# SCH_Avionic1_2026-04-20.net
KiCad netlist of a schematic drawn in EasyEDA
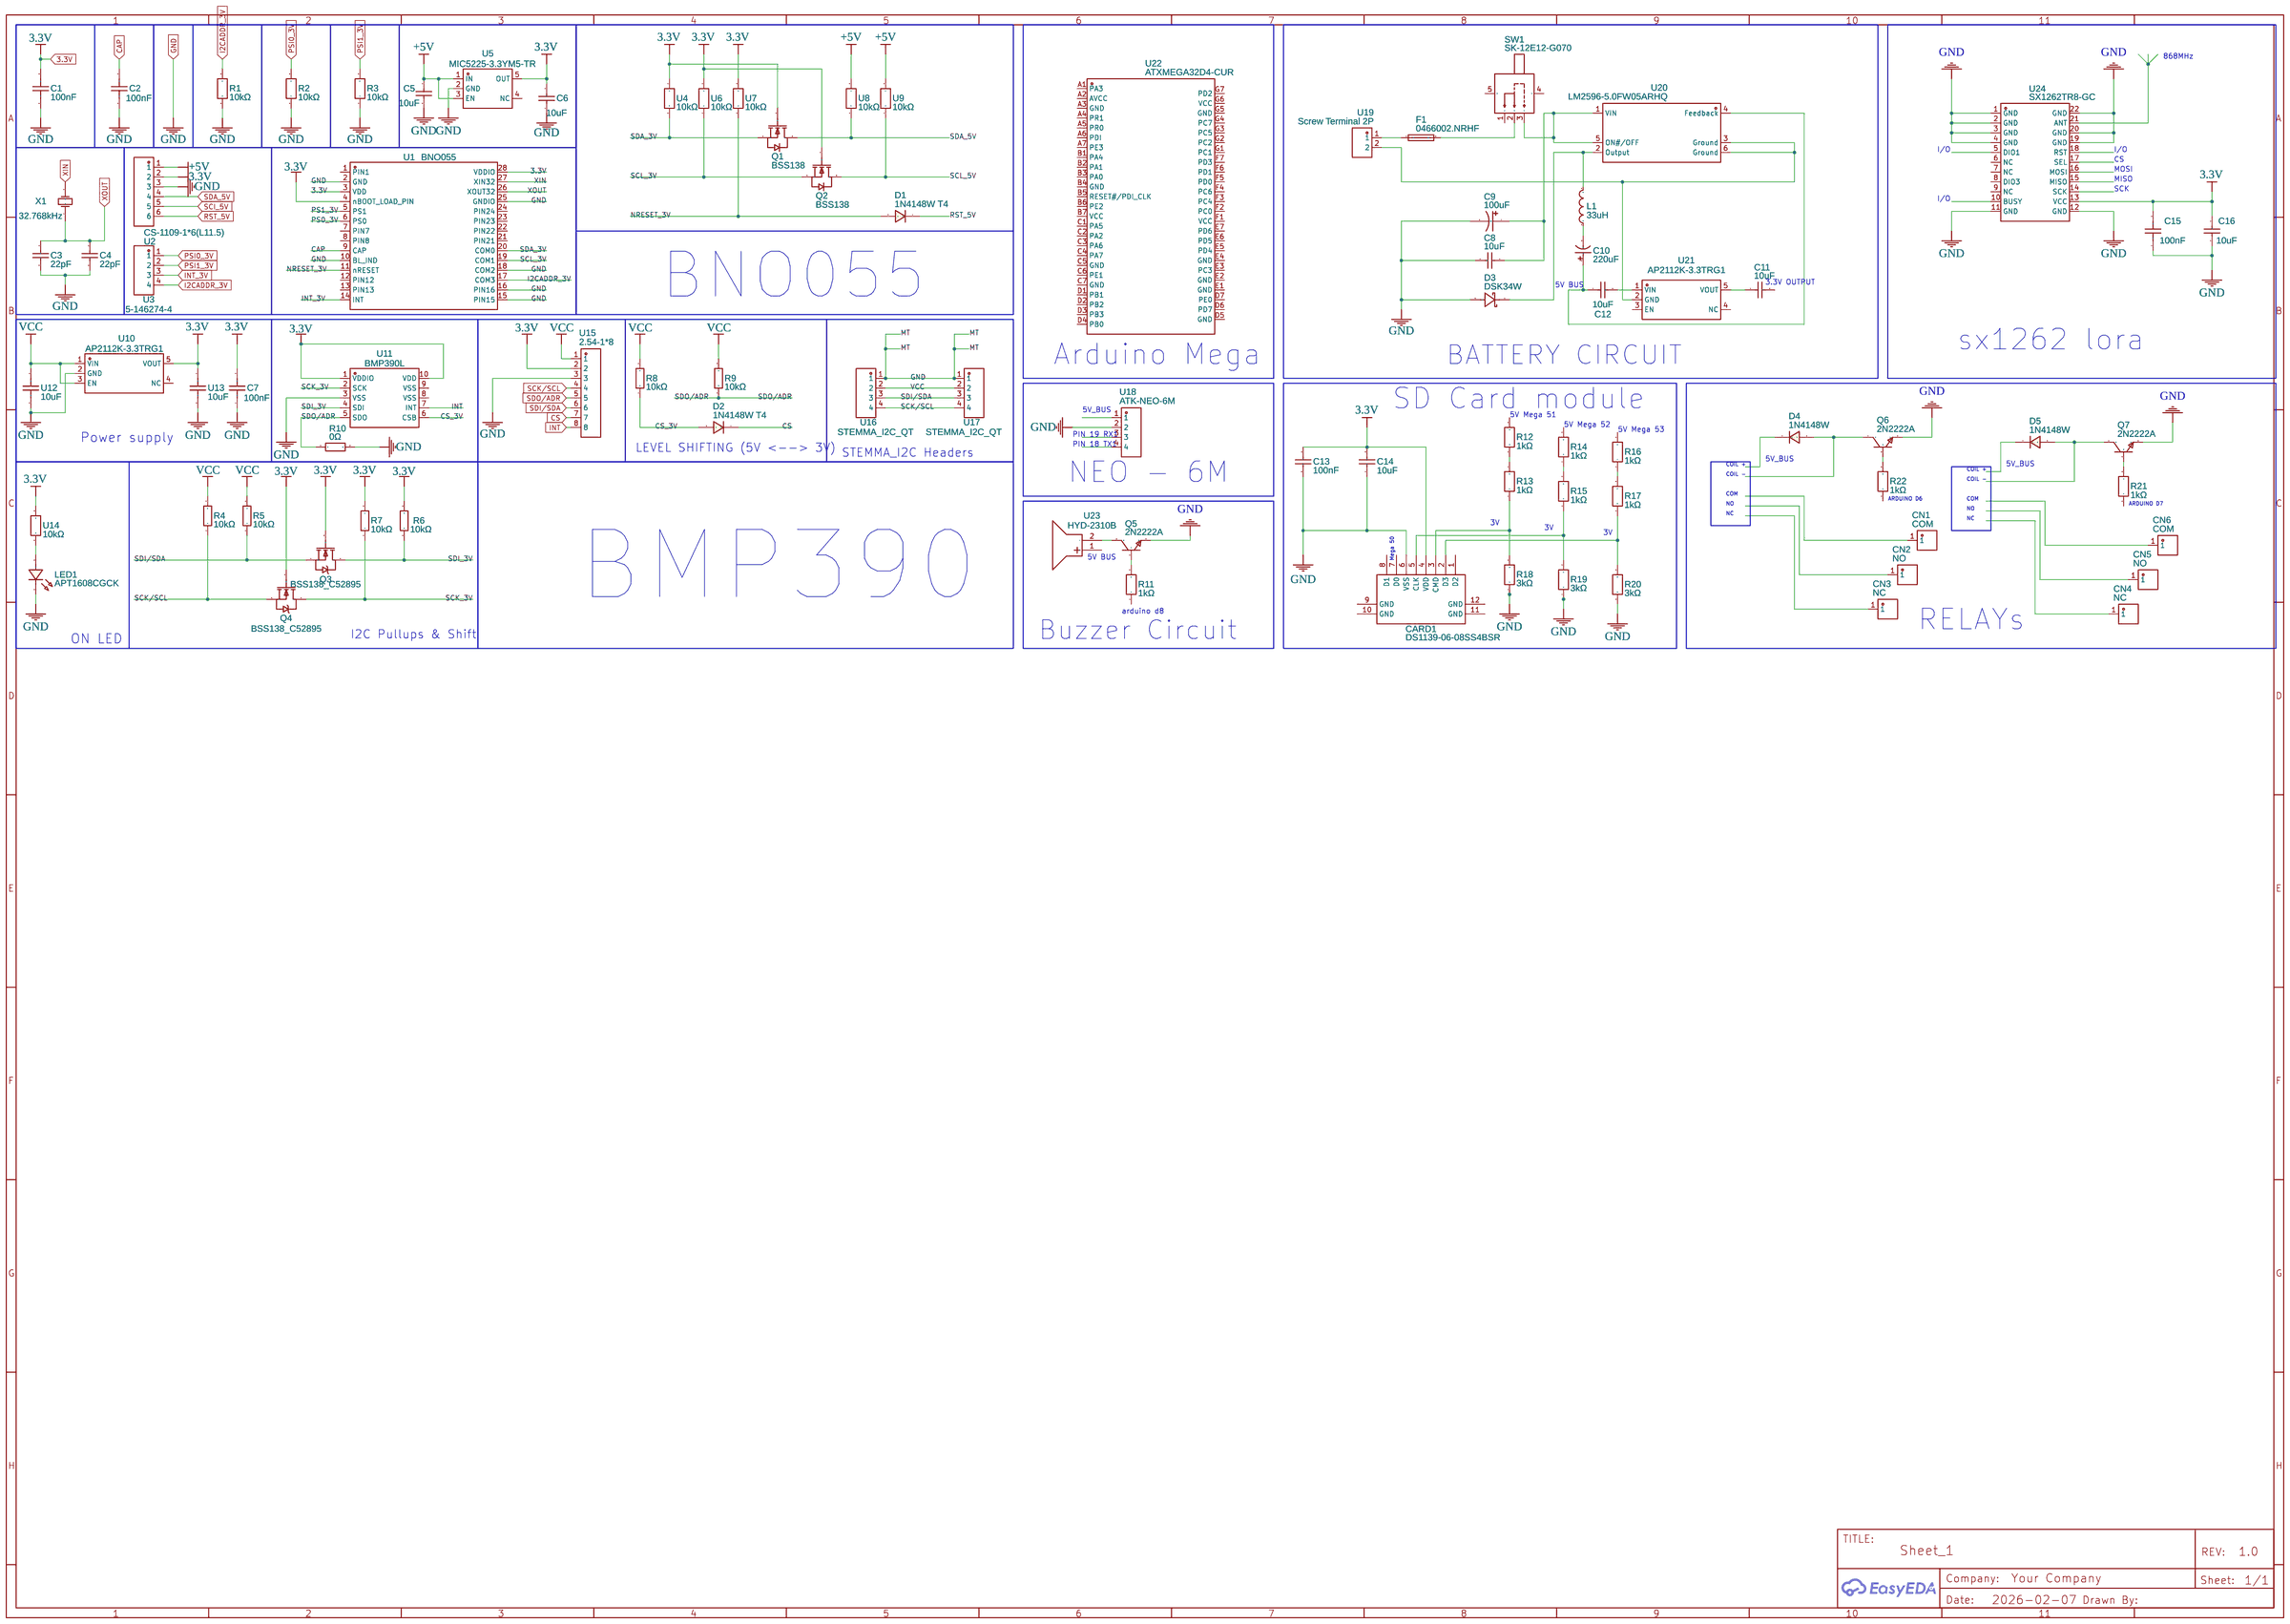
[diagram p0: schematic sheet]

(export (version "E")
  (design (tool "Eeschema 10.0.6"))
  (components
    (comp (ref "C1")
      (value "100nF")
      (fields
        (field (name "Manufacturer Part") "CL05B104KO5NNNC")
        (field (name "Manufacturer") "SAMSUNG(三星)")
      )
      (libsource (lib "") (part "CL05B104KO5NNNC"))
    )
    (comp (ref "C2")
      (value "100nF")
      (fields
        (field (name "Manufacturer Part") "CL05B104KO5NNNC")
        (field (name "Manufacturer") "SAMSUNG(三星)")
      )
      (libsource (lib "") (part "CL05B104KO5NNNC"))
    )
    (comp (ref "C3")
      (value "22pF")
      (fields
        (field (name "Manufacturer Part") "CL10C220JB8NNNC")
        (field (name "Manufacturer") "SAMSUNG(三星)")
      )
      (libsource (lib "") (part "CL10C220JB8NNNC"))
    )
    (comp (ref "C4")
      (value "22pF")
      (fields
        (field (name "Manufacturer Part") "CL10C220JB8NNNC")
        (field (name "Manufacturer") "SAMSUNG(三星)")
      )
      (libsource (lib "") (part "CL10C220JB8NNNC"))
    )
    (comp (ref "C5")
      (value "10uF")
      (fields
        (field (name "Manufacturer Part") "CL21A106KOQNNNE")
        (field (name "Manufacturer") "SAMSUNG(三星)")
      )
      (libsource (lib "") (part "CL21A106KOQNNNE_1"))
    )
    (comp (ref "C6")
      (value "10uF")
      (fields
        (field (name "Manufacturer Part") "CL21A106KOQNNNE")
        (field (name "Manufacturer") "SAMSUNG(三星)")
      )
      (libsource (lib "") (part "CL21A106KOQNNNE_2"))
    )
    (comp (ref "C7")
      (value "100nF")
      (fields
        (field (name "Manufacturer Part") "CC0402KRX5R6BB104")
        (field (name "Manufacturer") "YAGEO(国巨)")
      )
      (libsource (lib "") (part "CC0402KRX5R6BB104"))
    )
    (comp (ref "C8")
      (value "10uF")
      (fields
        (field (name "Manufacturer Part") "CL21A106KOQNNNE")
        (field (name "Manufacturer") "SAMSUNG(三星)")
      )
      (libsource (lib "") (part "CL21A106KOQNNNE"))
    )
    (comp (ref "C9")
      (value "100uF")
      (fields
        (field (name "Manufacturer Part") "NXA25V100M6.3*11 2.5TP")
        (field (name "Manufacturer") "SAMYOUNG(韩国三莹)")
      )
      (libsource (lib "") (part "NXA 25V100 6.3*11"))
    )
    (comp (ref "C10")
      (value "220uF")
      (fields
        (field (name "Manufacturer Part") "MHA 16V220 6.3*11")
        (field (name "Manufacturer") "SAMYOUNG(韩国三莹)")
      )
      (libsource (lib "") (part "MHA-16V220-6.3*11"))
    )
    (comp (ref "C11")
      (value "10uF")
      (fields
        (field (name "Manufacturer Part") "CL21A106KOQNNNE")
        (field (name "Manufacturer") "SAMSUNG(三星)")
      )
      (libsource (lib "") (part "CL21A106KOQNNNE"))
    )
    (comp (ref "C12")
      (value "10uF")
      (fields
        (field (name "Manufacturer Part") "CL21A106KOQNNNE")
        (field (name "Manufacturer") "SAMSUNG(三星)")
      )
      (libsource (lib "") (part "CL21A106KOQNNNE"))
    )
    (comp (ref "C13")
      (value "100nF")
      (fields
        (field (name "Manufacturer Part") "CL10B104KA8NNNC")
        (field (name "Manufacturer") "SAMSUNG(三星)")
      )
      (libsource (lib "") (part "CL10B104KA8NNNC"))
    )
    (comp (ref "C14")
      (value "10uF")
      (fields
        (field (name "Manufacturer Part") "CL21A106KOQNNNE")
        (field (name "Manufacturer") "SAMSUNG(三星)")
      )
      (libsource (lib "") (part "CL21A106KOQNNNE_2"))
    )
    (comp (ref "C15")
      (value "100nF")
      (fields
        (field (name "Manufacturer Part") "CL05B104KO5NNNC")
        (field (name "Manufacturer") "SAMSUNG(三星)")
      )
      (libsource (lib "") (part "CL05B104KO5NNNC"))
    )
    (comp (ref "C16")
      (value "10uF")
      (fields
        (field (name "Manufacturer Part") "CL21A106KOQNNNE")
        (field (name "Manufacturer") "SAMSUNG(三星)")
      )
      (libsource (lib "") (part "CL21A106KOQNNNE_1"))
    )
    (comp (ref "CARD1")
      (value "DS1139-06-08SS4BSR")
      (fields (field (name "Manufacturer") "CONNFLY"))
      (libsource (lib "") (part "DS1139-06-08SS4BSR"))
    )
    (comp (ref "CN1")
      (value "COM")
      (fields
        (field (name "Manufacturer Part") "DB2EK-5.08-3P-GN-S")
        (field (name "Manufacturer") "DORABO(地博电气)")
      )
      (libsource (lib "") (part "DB2EK-5.08-3P-GN-S"))
    )
    (comp (ref "CN2")
      (value "NO")
      (fields
        (field (name "Manufacturer Part") "DB2EK-5.08-3P-GN-S")
        (field (name "Manufacturer") "DORABO(地博电气)")
      )
      (libsource (lib "") (part "DB2EK-5.08-3P-GN-S"))
    )
    (comp (ref "CN3")
      (value "NC")
      (fields
        (field (name "Manufacturer Part") "DB2EK-5.08-3P-GN-S")
        (field (name "Manufacturer") "DORABO(地博电气)")
      )
      (libsource (lib "") (part "DB2EK-5.08-3P-GN-S"))
    )
    (comp (ref "CN4")
      (value "NC")
      (fields
        (field (name "Manufacturer Part") "DB2EK-5.08-3P-GN-S")
        (field (name "Manufacturer") "DORABO(地博电气)")
      )
      (libsource (lib "") (part "DB2EK-5.08-3P-GN-S"))
    )
    (comp (ref "CN5")
      (value "NO")
      (fields
        (field (name "Manufacturer Part") "DB2EK-5.08-3P-GN-S")
        (field (name "Manufacturer") "DORABO(地博电气)")
      )
      (libsource (lib "") (part "DB2EK-5.08-3P-GN-S"))
    )
    (comp (ref "CN6")
      (value "COM")
      (fields
        (field (name "Manufacturer Part") "DB2EK-5.08-3P-GN-S")
        (field (name "Manufacturer") "DORABO(地博电气)")
      )
      (libsource (lib "") (part "DB2EK-5.08-3P-GN-S"))
    )
    (comp (ref "D1")
      (value "1N4148W T4")
      (fields (field (name "Manufacturer Part") "1N4148W") (field (name "Manufacturer") "CJ(江苏长电/长晶)"))
      (libsource (lib "") (part "1N4148W T4"))
    )
    (comp (ref "D2")
      (value "1N4148W T4")
      (fields (field (name "Manufacturer Part") "1N4148W") (field (name "Manufacturer") "CJ(江苏长电/长晶)"))
      (libsource (lib "") (part "1N4148W T4"))
    )
    (comp (ref "D3")
      (value "DSK34W")
      (fields (field (name "Manufacturer") "FOSAN(富捷/富信)"))
      (libsource (lib "") (part "DSK34W"))
    )
    (comp (ref "D4")
      (value "1N4148W")
      (fields (field (name "Manufacturer") "HT(金誉)"))
      (libsource (lib "") (part "1N4148W"))
    )
    (comp (ref "D5")
      (value "1N4148W")
      (fields (field (name "Manufacturer") "HT(金誉)"))
      (libsource (lib "") (part "1N4148W"))
    )
    (comp (ref "F1")
      (value "0466002.NRHF")
      (fields (field (name "Manufacturer") "Littelfuse(美国力特)"))
      (libsource (lib "") (part "0466002.NRHF"))
    )
    (comp (ref "L1")
      (value "33uH")
      (fields (field (name "Manufacturer Part") "CKCS5040-33uH/M") (field (name "Manufacturer") "CENKER(岑科)"))
      (libsource (lib "") (part "CKCS5040-33UH/M"))
    )
    (comp (ref "LED1")
      (value "APT1608CGCK")
      (fields (field (name "Manufacturer") "Kingbright"))
      (libsource (lib "") (part "APT1608CGCK"))
    )
    (comp (ref "Q1")
      (value "BSS138")
      (fields (field (name "Manufacturer") "CJ(江苏长电/长晶)"))
      (libsource (lib "") (part "BSS138"))
    )
    (comp (ref "Q2")
      (value "BSS138")
      (fields (field (name "Manufacturer") "CJ(江苏长电/长晶)"))
      (libsource (lib "") (part "BSS138"))
    )
    (comp (ref "Q3")
      (value "BSS138_C52895")
      (fields (field (name "Manufacturer Part") "BSS138") (field (name "Manufacturer") "onsemi(安森美)"))
      (libsource (lib "") (part "BSS138_C52895"))
    )
    (comp (ref "Q4")
      (value "BSS138_C52895")
      (fields (field (name "Manufacturer Part") "BSS138") (field (name "Manufacturer") "onsemi(安森美)"))
      (libsource (lib "") (part "BSS138_C52895"))
    )
    (comp (ref "Q5")
      (value "2N2222A")
      (fields (field (name "Manufacturer") "BLUE ROCKET(蓝箭)"))
      (libsource (lib "") (part "2N2222A"))
    )
    (comp (ref "Q6")
      (value "2N2222A")
      (fields (field (name "Manufacturer") "BLUE ROCKET(蓝箭)"))
      (libsource (lib "") (part "2N2222A"))
    )
    (comp (ref "Q7")
      (value "2N2222A")
      (fields (field (name "Manufacturer") "BLUE ROCKET(蓝箭)"))
      (libsource (lib "") (part "2N2222A"))
    )
    (comp (ref "R1")
      (value "10kΩ")
      (fields (field (name "Manufacturer Part") "0402 ±1% 10K") (field (name "Manufacturer") "VO(翔胜)"))
      (libsource (lib "") (part "0402 ±1% 10K"))
    )
    (comp (ref "R2")
      (value "10kΩ")
      (fields (field (name "Manufacturer Part") "0402 ±1% 10K") (field (name "Manufacturer") "VO(翔胜)"))
      (libsource (lib "") (part "0402 ±1% 10K"))
    )
    (comp (ref "R3")
      (value "10kΩ")
      (fields (field (name "Manufacturer Part") "0402 ±1% 10K") (field (name "Manufacturer") "VO(翔胜)"))
      (libsource (lib "") (part "0402 ±1% 10K"))
    )
    (comp (ref "R4")
      (value "10kΩ")
      (fields
        (field (name "Manufacturer Part") "0603WAJ0103T5E")
        (field (name "Manufacturer") "UNI-ROYAL(厚声)")
      )
      (libsource (lib "") (part "0603WAJ0103T5E"))
    )
    (comp (ref "R5")
      (value "10kΩ")
      (fields
        (field (name "Manufacturer Part") "0603WAJ0103T5E")
        (field (name "Manufacturer") "UNI-ROYAL(厚声)")
      )
      (libsource (lib "") (part "0603WAJ0103T5E"))
    )
    (comp (ref "R6")
      (value "10kΩ")
      (fields
        (field (name "Manufacturer Part") "0603WAJ0103T5E")
        (field (name "Manufacturer") "UNI-ROYAL(厚声)")
      )
      (libsource (lib "") (part "0603WAJ0103T5E"))
    )
    (comp (ref "R7")
      (value "10kΩ")
      (fields
        (field (name "Manufacturer Part") "0603WAJ0103T5E")
        (field (name "Manufacturer") "UNI-ROYAL(厚声)")
      )
      (libsource (lib "") (part "0603WAJ0103T5E"))
    )
    (comp (ref "R8")
      (value "10kΩ")
      (fields
        (field (name "Manufacturer Part") "0603WAJ0103T5E")
        (field (name "Manufacturer") "UNI-ROYAL(厚声)")
      )
      (libsource (lib "") (part "0603WAJ0103T5E"))
    )
    (comp (ref "R9")
      (value "10kΩ")
      (fields
        (field (name "Manufacturer Part") "0603WAJ0103T5E")
        (field (name "Manufacturer") "UNI-ROYAL(厚声)")
      )
      (libsource (lib "") (part "0603WAJ0103T5E"))
    )
    (comp (ref "R10")
      (value "0Ω")
      (fields (field (name "Manufacturer Part") "RCT030RLF") (field (name "Manufacturer") "HKR(香港电阻)"))
      (libsource (lib "") (part "RCT030RJLF"))
    )
    (comp (ref "R11")
      (value "1kΩ")
      (fields (field (name "Manufacturer Part") "RCT021KFLF") (field (name "Manufacturer") "HKR(香港电阻)"))
      (libsource (lib "") (part "RCT021KFLF"))
    )
    (comp (ref "R12")
      (value "1kΩ")
      (fields (field (name "Manufacturer Part") "RCT021KFLF") (field (name "Manufacturer") "HKR(香港电阻)"))
      (libsource (lib "") (part "RCT021KFLF"))
    )
    (comp (ref "R13")
      (value "1kΩ")
      (fields (field (name "Manufacturer Part") "RCT021KFLF") (field (name "Manufacturer") "HKR(香港电阻)"))
      (libsource (lib "") (part "RCT021KFLF"))
    )
    (comp (ref "R14")
      (value "1kΩ")
      (fields (field (name "Manufacturer Part") "RCT021KFLF") (field (name "Manufacturer") "HKR(香港电阻)"))
      (libsource (lib "") (part "RCT021KFLF"))
    )
    (comp (ref "R15")
      (value "1kΩ")
      (fields (field (name "Manufacturer Part") "RCT021KFLF") (field (name "Manufacturer") "HKR(香港电阻)"))
      (libsource (lib "") (part "RCT021KFLF"))
    )
    (comp (ref "R16")
      (value "1kΩ")
      (fields (field (name "Manufacturer Part") "RCT021KFLF") (field (name "Manufacturer") "HKR(香港电阻)"))
      (libsource (lib "") (part "RCT021KFLF"))
    )
    (comp (ref "R17")
      (value "1kΩ")
      (fields (field (name "Manufacturer Part") "RCT021KFLF") (field (name "Manufacturer") "HKR(香港电阻)"))
      (libsource (lib "") (part "RCT021KFLF"))
    )
    (comp (ref "R18")
      (value "3kΩ")
      (fields (field (name "Manufacturer Part") "RCT023KFLF") (field (name "Manufacturer") "HKR(香港电阻)"))
      (libsource (lib "") (part "RCT023KFLF"))
    )
    (comp (ref "R19")
      (value "3kΩ")
      (fields (field (name "Manufacturer Part") "RCT023KFLF") (field (name "Manufacturer") "HKR(香港电阻)"))
      (libsource (lib "") (part "RCT023KFLF"))
    )
    (comp (ref "R20")
      (value "3kΩ")
      (fields (field (name "Manufacturer Part") "RCT023KFLF") (field (name "Manufacturer") "HKR(香港电阻)"))
      (libsource (lib "") (part "RCT023KFLF"))
    )
    (comp (ref "R21")
      (value "1kΩ")
      (fields (field (name "Manufacturer Part") "RCT021KFLF") (field (name "Manufacturer") "HKR(香港电阻)"))
      (libsource (lib "") (part "RCT021KFLF"))
    )
    (comp (ref "R22")
      (value "1kΩ")
      (fields (field (name "Manufacturer Part") "RCT021KFLF") (field (name "Manufacturer") "HKR(香港电阻)"))
      (libsource (lib "") (part "RCT021KFLF"))
    )
    (comp (ref "SW1")
      (value "SK-12E12-G070")
      (fields (field (name "Manufacturer") "G-Switch(品赞)"))
      (libsource (lib "") (part "SK-12E12-G070"))
    )
    (comp (ref "U1")
      (value "BNO055")
      (fields (field (name "Manufacturer") "Bosch(博世)"))
      (libsource (lib "") (part "BNO055"))
    )
    (comp (ref "U2")
      (value "CS-1109-1*6(L11.5)")
      (fields (field (name "Manufacturer") "CST(永丰盈)"))
      (libsource (lib "") (part "CS-1109-1*6(L11.5)"))
    )
    (comp (ref "U3")
      (value "5-146274-4")
      (fields (field (name "Manufacturer") "TE Connectivity(泰科电子)"))
      (libsource (lib "") (part "5-146274-4"))
    )
    (comp (ref "U4")
      (value "10kΩ")
      (fields
        (field (name "Manufacturer Part") "HoLTT0603-1/10W-10K-1%")
        (field (name "Manufacturer") "Milliohm(毫欧)")
      )
      (libsource (lib "") (part "HOLTT0603-1/10W-10K-1%_1"))
    )
    (comp (ref "U5")
      (value "MIC5225-3.3YM5-TR")
      (fields (field (name "Manufacturer") "MICROCHIP(美国微芯)"))
      (libsource (lib "") (part "MIC5225-3.3YM5-TR"))
    )
    (comp (ref "U6")
      (value "10kΩ")
      (fields
        (field (name "Manufacturer Part") "HoLTT0603-1/10W-10K-1%")
        (field (name "Manufacturer") "Milliohm(毫欧)")
      )
      (libsource (lib "") (part "HOLTT0603-1/10W-10K-1%"))
    )
    (comp (ref "U7")
      (value "10kΩ")
      (fields
        (field (name "Manufacturer Part") "HoLTT0603-1/10W-10K-1%")
        (field (name "Manufacturer") "Milliohm(毫欧)")
      )
      (libsource (lib "") (part "HOLTT0603-1/10W-10K-1%"))
    )
    (comp (ref "U8")
      (value "10kΩ")
      (fields
        (field (name "Manufacturer Part") "HoLTT0603-1/10W-10K-1%")
        (field (name "Manufacturer") "Milliohm(毫欧)")
      )
      (libsource (lib "") (part "HOLTT0603-1/10W-10K-1%"))
    )
    (comp (ref "U9")
      (value "10kΩ")
      (fields
        (field (name "Manufacturer Part") "HoLTT0603-1/10W-10K-1%")
        (field (name "Manufacturer") "Milliohm(毫欧)")
      )
      (libsource (lib "") (part "HOLTT0603-1/10W-10K-1%"))
    )
    (comp (ref "U10")
      (value "AP2112K-3.3TRG1")
      (fields (field (name "Manufacturer") "DIODES(美台)"))
      (libsource (lib "") (part "AP2112K-3.3TRG1"))
    )
    (comp (ref "U11")
      (value "BMP390L")
      (fields (field (name "Manufacturer") "Bosch(博世)"))
      (libsource (lib "") (part "BMP390L"))
    )
    (comp (ref "U12")
      (value "10uF")
      (fields
        (field (name "Manufacturer Part") "CC0805KKX7R6BB106")
        (field (name "Manufacturer") "YAGEO(国巨)")
      )
      (libsource (lib "") (part "CC0805KKX7R6BB106"))
    )
    (comp (ref "U13")
      (value "10uF")
      (fields
        (field (name "Manufacturer Part") "CC0805KKX7R6BB106")
        (field (name "Manufacturer") "YAGEO(国巨)")
      )
      (libsource (lib "") (part "CC0805KKX7R6BB106"))
    )
    (comp (ref "U14")
      (value "10kΩ")
      (fields
        (field (name "Manufacturer Part") "HoLTT0603-1/10W-10K-1%")
        (field (name "Manufacturer") "Milliohm(毫欧)")
      )
      (libsource (lib "") (part "HOLTT0603-1/10W-10K-1%"))
    )
    (comp (ref "U15")
      (value "2.54-1*8")
      (fields (field (name "Manufacturer") "ZHOURI(洲日)"))
      (libsource (lib "") (part "2.54-1*8"))
    )
    (comp (ref "U16")
      (value "STEMMA_I2C_QT")
      (fields
        (field (name "Manufacturer Part") "5-146274-4")
        (field (name "Manufacturer") "TE Connectivity(泰科电子)")
      )
      (libsource (lib "") (part "5-146274-4"))
    )
    (comp (ref "U17")
      (value "STEMMA_I2C_QT")
      (fields
        (field (name "Manufacturer Part") "5-146274-4")
        (field (name "Manufacturer") "TE Connectivity(泰科电子)")
      )
      (libsource (lib "") (part "5-146274-4_1"))
    )
    (comp (ref "U18") (value "ATK-NEO-6M") (libsource (lib "") (part "ATK-NEO-6M")))
    (comp (ref "U19")
      (value "Screw Terminal 2P")
      (fields
        (field (name "Manufacturer Part") "WJ500V-5.08-02P-13-00A")
        (field (name "Manufacturer") "KANGNEX(康奈克斯电气)")
      )
      (libsource (lib "") (part "WJ500V-5.08-2P-13-00A"))
    )
    (comp (ref "U20")
      (value "LM2596-5.0FW05ARHQ")
      (fields (field (name "Manufacturer") "GR(国睿)"))
      (libsource (lib "") (part "LM2596-5.0FW05ARHQ"))
    )
    (comp (ref "U21")
      (value "AP2112K-3.3TRG1")
      (fields (field (name "Manufacturer") "DIODES(美台)"))
      (libsource (lib "") (part "AP2112K-3.3TRG1"))
    )
    (comp (ref "U22") (value "ATXMEGA32D4-CUR") (libsource (lib "") (part "ATXMEGA32D4-CUR")))
    (comp (ref "U23")
      (value "HYD-2310B")
      (fields (field (name "Manufacturer") "HYDZ(华宇)"))
      (libsource (lib "") (part "HYD-2310B"))
    )
    (comp (ref "U24")
      (value "SX1262TR8-GC")
      (fields (field (name "Manufacturer") "Silicontra(硅传科技)"))
      (libsource (lib "") (part "SX1262TR8-GC"))
    )
    (comp (ref "X1")
      (value "32.768kHz")
      (fields (field (name "Manufacturer Part") "X206032768KGB2SC") (field (name "Manufacturer") "YXC(扬兴晶振)"))
      (libsource (lib "") (part "X206032768KGB2SC"))
    )
  )
  (nets
    (net (code "1") (name "+5V") (class "Default")
      (node (ref "C5") (pin "1") (pinfunction "1_1") (pintype "input"))
      (node (ref "U2") (pin "1") (pinfunction "1_1") (pintype "unspecified"))
      (node (ref "U5") (pin "1") (pinfunction "IN_1") (pintype "unspecified"))
      (node (ref "U5") (pin "3") (pinfunction "EN_3") (pintype "unspecified"))
      (node (ref "U8") (pin "2") (pinfunction "2_2") (pintype "unspecified"))
      (node (ref "U9") (pin "2") (pinfunction "2_2") (pintype "unspecified"))
    )
    (net (code "2") (name "/CS_3V") (class "Default")
      (node (ref "D2") (pin "2") (pinfunction "A_2") (pintype "unspecified"))
      (node (ref "R8") (pin "1") (pinfunction "1_1") (pintype "input"))
      (node (ref "U11") (pin "6") (pinfunction "CSB_6") (pintype "unspecified"))
    )
    (net (code "3") (name "/NRESET_3V") (class "Default")
      (node (ref "D1") (pin "2") (pinfunction "A_2") (pintype "unspecified"))
      (node (ref "U1") (pin "11") (pinfunction "nRESET_11") (pintype "unspecified"))
      (node (ref "U7") (pin "1") (pinfunction "1_1") (pintype "unspecified"))
    )
    (net (code "4") (name "/PS0_3V") (class "Default")
      (node (ref "U1") (pin "6") (pinfunction "PS0_6") (pintype "unspecified"))
    )
    (net (code "5") (name "/PS1_3V") (class "Default")
      (node (ref "U1") (pin "5") (pinfunction "PS1_5") (pintype "unspecified"))
    )
    (net (code "6") (name "/SCK_3V") (class "Default")
      (node (ref "Q4") (pin "3") (pinfunction "D_3") (pintype "unspecified"))
      (node (ref "R7") (pin "1") (pinfunction "1_1") (pintype "input"))
      (node (ref "U11") (pin "2") (pinfunction "SCK_2") (pintype "unspecified"))
    )
    (net (code "7") (name "/SCL_3V") (class "Default")
      (node (ref "Q2") (pin "2") (pinfunction "S_2") (pintype "unspecified"))
      (node (ref "U1") (pin "19") (pinfunction "COM1_19") (pintype "unspecified"))
      (node (ref "U6") (pin "1") (pinfunction "1_1") (pintype "unspecified"))
    )
    (net (code "8") (name "/SCL_5V") (class "Default")
      (node (ref "Q2") (pin "3") (pinfunction "D_3") (pintype "unspecified"))
      (node (ref "U9") (pin "1") (pinfunction "1_1") (pintype "unspecified"))
    )
    (net (code "9") (name "/SDA_3V") (class "Default")
      (node (ref "Q1") (pin "2") (pinfunction "S_2") (pintype "unspecified"))
      (node (ref "U1") (pin "20") (pinfunction "COM0_20") (pintype "unspecified"))
      (node (ref "U4") (pin "2") (pinfunction "2_2") (pintype "unspecified"))
    )
    (net (code "10") (name "/SDI_3V") (class "Default")
      (node (ref "Q3") (pin "3") (pinfunction "D_3") (pintype "unspecified"))
      (node (ref "R6") (pin "1") (pinfunction "1_1") (pintype "input"))
      (node (ref "U11") (pin "4") (pinfunction "SDI_4") (pintype "unspecified"))
    )
    (net (code "11") (name "3.3V") (class "Default")
      (node (ref "C1") (pin "2") (pinfunction "2_2") (pintype "unspecified"))
      (node (ref "C13") (pin "1") (pinfunction "1_1") (pintype "input"))
      (node (ref "C14") (pin "2") (pinfunction "2_2") (pintype "input"))
      (node (ref "C15") (pin "2") (pinfunction "2_2") (pintype "unspecified"))
      (node (ref "C16") (pin "1") (pinfunction "1_1") (pintype "input"))
      (node (ref "C6") (pin "2") (pinfunction "2_2") (pintype "input"))
      (node (ref "C7") (pin "2") (pinfunction "2_2") (pintype "unspecified"))
      (node (ref "CARD1") (pin "4") (pinfunction "VDD_4") (pintype "unspecified"))
      (node (ref "Q1") (pin "1") (pinfunction "G_1") (pintype "unspecified"))
      (node (ref "Q2") (pin "1") (pinfunction "G_1") (pintype "unspecified"))
      (node (ref "Q3") (pin "1") (pinfunction "G_1") (pintype "unspecified"))
      (node (ref "Q4") (pin "1") (pinfunction "G_1") (pintype "unspecified"))
      (node (ref "R6") (pin "2") (pinfunction "2_2") (pintype "input"))
      (node (ref "R7") (pin "2") (pinfunction "2_2") (pintype "input"))
      (node (ref "U1") (pin "28") (pinfunction "VDDIO_28") (pintype "unspecified"))
      (node (ref "U1") (pin "3") (pinfunction "VDD_3") (pintype "unspecified"))
      (node (ref "U1") (pin "4") (pinfunction "nBOOT_LOAD_PIN_4") (pintype "unspecified"))
      (node (ref "U10") (pin "5") (pinfunction "VOUT_5") (pintype "unspecified"))
      (node (ref "U11") (pin "1") (pinfunction "VDDIO_1") (pintype "unspecified"))
      (node (ref "U11") (pin "10") (pinfunction "VDD_10") (pintype "unspecified"))
      (node (ref "U13") (pin "1") (pinfunction "1_1") (pintype "unspecified"))
      (node (ref "U14") (pin "2") (pinfunction "2_2") (pintype "unspecified"))
      (node (ref "U15") (pin "2") (pinfunction "2_2") (pintype "unspecified"))
      (node (ref "U2") (pin "2") (pinfunction "2_2") (pintype "unspecified"))
      (node (ref "U24") (pin "13") (pinfunction "VCC_13") (pintype "unspecified"))
      (node (ref "U4") (pin "1") (pinfunction "1_1") (pintype "unspecified"))
      (node (ref "U5") (pin "5") (pinfunction "OUT_5") (pintype "unspecified"))
      (node (ref "U6") (pin "2") (pinfunction "2_2") (pintype "unspecified"))
      (node (ref "U7") (pin "2") (pinfunction "2_2") (pintype "unspecified"))
    )
    (net (code "12") (name "CAP") (class "Default")
      (node (ref "C2") (pin "2") (pinfunction "2_2") (pintype "unspecified"))
      (node (ref "U1") (pin "9") (pinfunction "CAP_9") (pintype "unspecified"))
    )
    (net (code "13") (name "CS") (class "Default")
      (node (ref "D2") (pin "1") (pinfunction "K_1") (pintype "unspecified"))
      (node (ref "U15") (pin "7") (pinfunction "7_7") (pintype "unspecified"))
    )
    (net (code "14") (name "GND") (class "Default")
      (node (ref "C1") (pin "1") (pinfunction "1_1") (pintype "unspecified"))
      (node (ref "C13") (pin "2") (pinfunction "2_2") (pintype "input"))
      (node (ref "C14") (pin "1") (pinfunction "1_1") (pintype "input"))
      (node (ref "C15") (pin "1") (pinfunction "1_1") (pintype "unspecified"))
      (node (ref "C16") (pin "2") (pinfunction "2_2") (pintype "input"))
      (node (ref "C2") (pin "1") (pinfunction "1_1") (pintype "unspecified"))
      (node (ref "C3") (pin "1") (pinfunction "1_1") (pintype "input"))
      (node (ref "C4") (pin "1") (pinfunction "1_1") (pintype "input"))
      (node (ref "C5") (pin "2") (pinfunction "2_2") (pintype "input"))
      (node (ref "C6") (pin "1") (pinfunction "1_1") (pintype "input"))
      (node (ref "C7") (pin "1") (pinfunction "1_1") (pintype "unspecified"))
      (node (ref "C8") (pin "1") (pinfunction "1_1") (pintype "input"))
      (node (ref "C9") (pin "2") (pinfunction "2_2") (pintype "unspecified"))
      (node (ref "CARD1") (pin "6") (pinfunction "VSS_6") (pintype "unspecified"))
      (node (ref "D3") (pin "2") (pinfunction "A_2") (pintype "unspecified"))
      (node (ref "LED1") (pin "2") (pinfunction "K_2") (pintype "unspecified"))
      (node (ref "Q5") (pin "3") (pinfunction "E_3") (pintype "unspecified"))
      (node (ref "Q6") (pin "3") (pinfunction "E_3") (pintype "unspecified"))
      (node (ref "Q7") (pin "3") (pinfunction "E_3") (pintype "unspecified"))
      (node (ref "R1") (pin "1") (pinfunction "1_1") (pintype "unspecified"))
      (node (ref "R10") (pin "2") (pinfunction "2_2") (pintype "unspecified"))
      (node (ref "R18") (pin "1") (pinfunction "1_1") (pintype "unspecified"))
      (node (ref "R19") (pin "1") (pinfunction "1_1") (pintype "unspecified"))
      (node (ref "R2") (pin "1") (pinfunction "1_1") (pintype "unspecified"))
      (node (ref "R20") (pin "1") (pinfunction "1_1") (pintype "unspecified"))
      (node (ref "R3") (pin "1") (pinfunction "1_1") (pintype "unspecified"))
      (node (ref "U1") (pin "10") (pinfunction "BL_IND_10") (pintype "unspecified"))
      (node (ref "U1") (pin "15") (pinfunction "PIN15_15") (pintype "unspecified"))
      (node (ref "U1") (pin "16") (pinfunction "PIN16_16") (pintype "unspecified"))
      (node (ref "U1") (pin "18") (pinfunction "COM2_18") (pintype "unspecified"))
      (node (ref "U1") (pin "2") (pinfunction "GND_2") (pintype "unspecified"))
      (node (ref "U1") (pin "25") (pinfunction "GNDIO_25") (pintype "unspecified"))
      (node (ref "U10") (pin "2") (pinfunction "GND_2") (pintype "unspecified"))
      (node (ref "U11") (pin "3") (pinfunction "VSS_3") (pintype "unspecified"))
      (node (ref "U12") (pin "2") (pinfunction "2_2") (pintype "unspecified"))
      (node (ref "U13") (pin "2") (pinfunction "2_2") (pintype "unspecified"))
      (node (ref "U15") (pin "3") (pinfunction "3_3") (pintype "unspecified"))
      (node (ref "U16") (pin "1") (pinfunction "1_1") (pintype "unspecified"))
      (node (ref "U17") (pin "1") (pinfunction "1_1") (pintype "unspecified"))
      (node (ref "U18") (pin "2") (pinfunction "2_2") (pintype "unspecified"))
      (node (ref "U2") (pin "3") (pinfunction "3_3") (pintype "unspecified"))
      (node (ref "U24") (pin "1") (pinfunction "GND_1") (pintype "unspecified"))
      (node (ref "U24") (pin "11") (pinfunction "GND_11") (pintype "unspecified"))
      (node (ref "U24") (pin "12") (pinfunction "GND_12") (pintype "unspecified"))
      (node (ref "U24") (pin "19") (pinfunction "GND_19") (pintype "unspecified"))
      (node (ref "U24") (pin "2") (pinfunction "GND_2") (pintype "unspecified"))
      (node (ref "U24") (pin "20") (pinfunction "GND_20") (pintype "unspecified"))
      (node (ref "U24") (pin "22") (pinfunction "GND_22") (pintype "unspecified"))
      (node (ref "U24") (pin "3") (pinfunction "GND_3") (pintype "unspecified"))
      (node (ref "U24") (pin "4") (pinfunction "GND_4") (pintype "unspecified"))
      (node (ref "U5") (pin "2") (pinfunction "GND_2") (pintype "unspecified"))
    )
    (net (code "15") (name "I2CADDR_3V") (class "Default")
      (node (ref "R1") (pin "2") (pinfunction "2_2") (pintype "unspecified"))
      (node (ref "U1") (pin "17") (pinfunction "COM3_17") (pintype "unspecified"))
      (node (ref "U3") (pin "4") (pinfunction "4_4") (pintype "unspecified"))
    )
    (net (code "16") (name "INT") (class "Default")
      (node (ref "U11") (pin "7") (pinfunction "INT_7") (pintype "unspecified"))
      (node (ref "U15") (pin "8") (pinfunction "8_8") (pintype "unspecified"))
    )
    (net (code "17") (name "INT_3V") (class "Default")
      (node (ref "U1") (pin "14") (pinfunction "INT_14") (pintype "unspecified"))
      (node (ref "U3") (pin "3") (pinfunction "3_3") (pintype "unspecified"))
    )
    (net (code "18") (name "Net-(C10-Pad2)") (class "Default")
      (node (ref "C10") (pin "2") (pinfunction "2_2") (pintype "input"))
      (node (ref "L1") (pin "1") (pinfunction "1_1") (pintype "unspecified"))
    )
    (net (code "19") (name "Net-(CARD1-CLK)") (class "Default")
      (node (ref "CARD1") (pin "5") (pinfunction "CLK_5") (pintype "unspecified"))
      (node (ref "R15") (pin "1") (pinfunction "1_1") (pintype "unspecified"))
      (node (ref "R19") (pin "2") (pinfunction "2_2") (pintype "unspecified"))
    )
    (net (code "20") (name "Net-(CARD1-CMD)") (class "Default")
      (node (ref "CARD1") (pin "3") (pinfunction "CMD_3") (pintype "unspecified"))
      (node (ref "R13") (pin "1") (pinfunction "1_1") (pintype "unspecified"))
      (node (ref "R18") (pin "2") (pinfunction "2_2") (pintype "unspecified"))
    )
    (net (code "21") (name "Net-(CARD1-D3)") (class "Default")
      (node (ref "CARD1") (pin "2") (pinfunction "D3_2") (pintype "unspecified"))
      (node (ref "R17") (pin "1") (pinfunction "1_1") (pintype "unspecified"))
      (node (ref "R20") (pin "2") (pinfunction "2_2") (pintype "unspecified"))
    )
    (net (code "22") (name "Net-(D3-K)") (class "Default")
      (node (ref "D3") (pin "1") (pinfunction "K_1") (pintype "unspecified"))
      (node (ref "L1") (pin "2") (pinfunction "2_2") (pintype "unspecified"))
      (node (ref "U20") (pin "2") (pinfunction "Output_2") (pintype "unspecified"))
    )
    (net (code "23") (name "Net-(D4-A)") (class "Default")
      (node (ref "D4") (pin "2") (pinfunction "A_2") (pintype "unspecified"))
      (node (ref "Q6") (pin "1") (pinfunction "C_1") (pintype "unspecified"))
    )
    (net (code "24") (name "Net-(D5-A)") (class "Default")
      (node (ref "D5") (pin "2") (pinfunction "A_2") (pintype "unspecified"))
      (node (ref "Q7") (pin "1") (pinfunction "C_1") (pintype "unspecified"))
    )
    (net (code "25") (name "Net-(F1-Pad1)") (class "Default")
      (node (ref "F1") (pin "1") (pinfunction "1_1") (pintype "unspecified"))
      (node (ref "U19") (pin "1") (pinfunction "1_1") (pintype "unspecified"))
    )
    (net (code "26") (name "Net-(F1-Pad2)") (class "Default")
      (node (ref "F1") (pin "2") (pinfunction "2_2") (pintype "unspecified"))
      (node (ref "SW1") (pin "2") (pinfunction "2_2") (pintype "unspecified"))
    )
    (net (code "27") (name "Net-(LED1-A)") (class "Default")
      (node (ref "LED1") (pin "1") (pinfunction "A_1") (pintype "unspecified"))
      (node (ref "U14") (pin "1") (pinfunction "1_1") (pintype "unspecified"))
    )
    (net (code "28") (name "Net-(Q5-B)") (class "Default")
      (node (ref "Q5") (pin "2") (pinfunction "B_2") (pintype "unspecified"))
      (node (ref "R11") (pin "2") (pinfunction "2_2") (pintype "unspecified"))
    )
    (net (code "29") (name "Net-(Q5-C)") (class "Default")
      (node (ref "Q5") (pin "1") (pinfunction "C_1") (pintype "unspecified"))
      (node (ref "U23") (pin "2") (pinfunction "-_2") (pintype "unspecified"))
    )
    (net (code "30") (name "Net-(Q6-B)") (class "Default")
      (node (ref "Q6") (pin "2") (pinfunction "B_2") (pintype "unspecified"))
      (node (ref "R22") (pin "2") (pinfunction "2_2") (pintype "unspecified"))
    )
    (net (code "31") (name "Net-(Q7-B)") (class "Default")
      (node (ref "Q7") (pin "2") (pinfunction "B_2") (pintype "unspecified"))
      (node (ref "R21") (pin "2") (pinfunction "2_2") (pintype "unspecified"))
    )
    (net (code "32") (name "Net-(R12-Pad1)") (class "Default")
      (node (ref "R12") (pin "1") (pinfunction "1_1") (pintype "unspecified"))
      (node (ref "R13") (pin "2") (pinfunction "2_2") (pintype "unspecified"))
    )
    (net (code "33") (name "Net-(R14-Pad1)") (class "Default")
      (node (ref "R14") (pin "1") (pinfunction "1_1") (pintype "unspecified"))
      (node (ref "R15") (pin "2") (pinfunction "2_2") (pintype "unspecified"))
    )
    (net (code "34") (name "Net-(R16-Pad1)") (class "Default")
      (node (ref "R16") (pin "1") (pinfunction "1_1") (pintype "unspecified"))
      (node (ref "R17") (pin "2") (pinfunction "2_2") (pintype "unspecified"))
    )
    (net (code "35") (name "Net-(U20-Feedback)") (class "Default")
      (node (ref "C10") (pin "1") (pinfunction "1_1") (pintype "input"))
      (node (ref "C12") (pin "1") (pinfunction "1_1") (pintype "input"))
      (node (ref "U20") (pin "4") (pinfunction "Feedback_4") (pintype "unspecified"))
    )
    (net (code "36") (name "Net-(U20-ON#{slash}OFF)") (class "Default")
      (node (ref "C8") (pin "2") (pinfunction "2_2") (pintype "input"))
      (node (ref "C9") (pin "1") (pinfunction "1_1") (pintype "unspecified"))
      (node (ref "SW1") (pin "3") (pinfunction "3_3") (pintype "unspecified"))
      (node (ref "U20") (pin "1") (pinfunction "VIN_1") (pintype "unspecified"))
      (node (ref "U20") (pin "5") (pinfunction "ON#/OFF_5") (pintype "unspecified"))
    )
    (net (code "37") (name "Net-(U21-GND)") (class "Default")
      (node (ref "U19") (pin "2") (pinfunction "2_2") (pintype "unspecified"))
      (node (ref "U20") (pin "3") (pinfunction "Ground_3") (pintype "unspecified"))
      (node (ref "U20") (pin "6") (pinfunction "Ground_6") (pintype "unspecified"))
      (node (ref "U21") (pin "2") (pinfunction "GND_2") (pintype "unspecified"))
    )
    (net (code "38") (name "Net-(U21-VIN)") (class "Default")
      (node (ref "C12") (pin "2") (pinfunction "2_2") (pintype "input"))
      (node (ref "U21") (pin "1") (pinfunction "VIN_1") (pintype "unspecified"))
    )
    (net (code "39") (name "Net-(U21-VOUT)") (class "Default")
      (node (ref "C11") (pin "1") (pinfunction "1_1") (pintype "input"))
      (node (ref "U21") (pin "5") (pinfunction "VOUT_5") (pintype "unspecified"))
    )
    (net (code "40") (name "PSI0_3V") (class "Default")
      (node (ref "R2") (pin "2") (pinfunction "2_2") (pintype "unspecified"))
      (node (ref "U3") (pin "1") (pinfunction "1_1") (pintype "unspecified"))
    )
    (net (code "41") (name "PSI1_3V") (class "Default")
      (node (ref "R3") (pin "2") (pinfunction "2_2") (pintype "unspecified"))
      (node (ref "U3") (pin "2") (pinfunction "2_2") (pintype "unspecified"))
    )
    (net (code "42") (name "RST_5V") (class "Default")
      (node (ref "D1") (pin "1") (pinfunction "K_1") (pintype "unspecified"))
      (node (ref "U2") (pin "6") (pinfunction "6_6") (pintype "unspecified"))
    )
    (net (code "43") (name "SCI_5V") (class "Default")
      (node (ref "U2") (pin "5") (pinfunction "5_5") (pintype "unspecified"))
    )
    (net (code "44") (name "SCK{slash}SCL") (class "Default")
      (node (ref "Q4") (pin "2") (pinfunction "S_2") (pintype "unspecified"))
      (node (ref "R4") (pin "1") (pinfunction "1_1") (pintype "input"))
      (node (ref "U15") (pin "4") (pinfunction "4_4") (pintype "unspecified"))
      (node (ref "U16") (pin "4") (pinfunction "4_4") (pintype "unspecified"))
      (node (ref "U17") (pin "4") (pinfunction "4_4") (pintype "unspecified"))
    )
    (net (code "45") (name "SDA_5V") (class "Default")
      (node (ref "Q1") (pin "3") (pinfunction "D_3") (pintype "unspecified"))
      (node (ref "U2") (pin "4") (pinfunction "4_4") (pintype "unspecified"))
      (node (ref "U8") (pin "1") (pinfunction "1_1") (pintype "unspecified"))
    )
    (net (code "46") (name "SDI{slash}SDA") (class "Default")
      (node (ref "Q3") (pin "2") (pinfunction "S_2") (pintype "unspecified"))
      (node (ref "R5") (pin "1") (pinfunction "1_1") (pintype "input"))
      (node (ref "U15") (pin "6") (pinfunction "6_6") (pintype "unspecified"))
      (node (ref "U16") (pin "3") (pinfunction "3_3") (pintype "unspecified"))
      (node (ref "U17") (pin "3") (pinfunction "3_3") (pintype "unspecified"))
    )
    (net (code "47") (name "SDO{slash}ADR") (class "Default")
      (node (ref "R10") (pin "1") (pinfunction "1_1") (pintype "unspecified"))
      (node (ref "R9") (pin "1") (pinfunction "1_1") (pintype "input"))
      (node (ref "U11") (pin "5") (pinfunction "SDO_5") (pintype "unspecified"))
      (node (ref "U15") (pin "5") (pinfunction "5_5") (pintype "unspecified"))
    )
    (net (code "48") (name "VCC") (class "Default")
      (node (ref "R4") (pin "2") (pinfunction "2_2") (pintype "input"))
      (node (ref "R5") (pin "2") (pinfunction "2_2") (pintype "input"))
      (node (ref "R8") (pin "2") (pinfunction "2_2") (pintype "input"))
      (node (ref "R9") (pin "2") (pinfunction "2_2") (pintype "input"))
      (node (ref "U10") (pin "1") (pinfunction "VIN_1") (pintype "unspecified"))
      (node (ref "U10") (pin "3") (pinfunction "EN_3") (pintype "unspecified"))
      (node (ref "U12") (pin "1") (pinfunction "1_1") (pintype "unspecified"))
      (node (ref "U15") (pin "1") (pinfunction "1_1") (pintype "unspecified"))
      (node (ref "U16") (pin "2") (pinfunction "2_2") (pintype "unspecified"))
      (node (ref "U17") (pin "2") (pinfunction "2_2") (pintype "unspecified"))
    )
    (net (code "49") (name "XIN") (class "Default")
      (node (ref "U1") (pin "27") (pinfunction "XIN32_27") (pintype "unspecified"))
      (node (ref "X1") (pin "2") (pinfunction "OSC2_2") (pintype "unspecified"))
    )
    (net (code "50") (name "XOUT") (class "Default")
      (node (ref "C3") (pin "2") (pinfunction "2_2") (pintype "input"))
      (node (ref "C4") (pin "2") (pinfunction "2_2") (pintype "input"))
      (node (ref "U1") (pin "26") (pinfunction "XOUT32_26") (pintype "unspecified"))
      (node (ref "X1") (pin "1") (pinfunction "OSC1_1") (pintype "unspecified"))
    )
    (net (code "51") (name "unconnected-(C11-Pad2)") (class "Default")
      (node (ref "C11") (pin "2") (pinfunction "2_2") (pintype "input"))
    )
    (net (code "52") (name "unconnected-(CARD1-D0-Pad7)") (class "Default")
      (node (ref "CARD1") (pin "7") (pinfunction "D0_7") (pintype "unspecified"))
    )
    (net (code "53") (name "unconnected-(CARD1-D1-Pad8)") (class "Default")
      (node (ref "CARD1") (pin "8") (pinfunction "D1_8") (pintype "unspecified"))
    )
    (net (code "54") (name "unconnected-(CARD1-D2-Pad1)") (class "Default")
      (node (ref "CARD1") (pin "1") (pinfunction "D2_1") (pintype "unspecified"))
    )
    (net (code "55") (name "unconnected-(CARD1-GND-Pad9)") (class "Default")
      (node (ref "CARD1") (pin "9") (pinfunction "GND_9") (pintype "unspecified"))
    )
    (net (code "56") (name "unconnected-(CARD1-GND-Pad10)") (class "Default")
      (node (ref "CARD1") (pin "10") (pinfunction "GND_10") (pintype "unspecified"))
    )
    (net (code "57") (name "unconnected-(CARD1-GND-Pad11)") (class "Default")
      (node (ref "CARD1") (pin "11") (pinfunction "GND_11") (pintype "unspecified"))
    )
    (net (code "58") (name "unconnected-(CARD1-GND-Pad12)") (class "Default")
      (node (ref "CARD1") (pin "12") (pinfunction "GND_12") (pintype "unspecified"))
    )
    (net (code "59") (name "unconnected-(CN1-Pad1)") (class "Default")
      (node (ref "CN1") (pin "1") (pinfunction "1_1") (pintype "unspecified"))
    )
    (net (code "60") (name "unconnected-(CN2-Pad1)") (class "Default")
      (node (ref "CN2") (pin "1") (pinfunction "1_1") (pintype "unspecified"))
    )
    (net (code "61") (name "unconnected-(CN3-Pad1)") (class "Default")
      (node (ref "CN3") (pin "1") (pinfunction "1_1") (pintype "unspecified"))
    )
    (net (code "62") (name "unconnected-(CN4-Pad1)") (class "Default")
      (node (ref "CN4") (pin "1") (pinfunction "1_1") (pintype "unspecified"))
    )
    (net (code "63") (name "unconnected-(CN5-Pad1)") (class "Default")
      (node (ref "CN5") (pin "1") (pinfunction "1_1") (pintype "unspecified"))
    )
    (net (code "64") (name "unconnected-(CN6-Pad1)") (class "Default")
      (node (ref "CN6") (pin "1") (pinfunction "1_1") (pintype "unspecified"))
    )
    (net (code "65") (name "unconnected-(D4-K-Pad1)") (class "Default")
      (node (ref "D4") (pin "1") (pinfunction "K_1") (pintype "unspecified"))
    )
    (net (code "66") (name "unconnected-(D5-K-Pad1)") (class "Default")
      (node (ref "D5") (pin "1") (pinfunction "K_1") (pintype "unspecified"))
    )
    (net (code "67") (name "unconnected-(R11-Pad1)") (class "Default")
      (node (ref "R11") (pin "1") (pinfunction "1_1") (pintype "unspecified"))
    )
    (net (code "68") (name "unconnected-(R12-Pad2)") (class "Default")
      (node (ref "R12") (pin "2") (pinfunction "2_2") (pintype "unspecified"))
    )
    (net (code "69") (name "unconnected-(R14-Pad2)") (class "Default")
      (node (ref "R14") (pin "2") (pinfunction "2_2") (pintype "unspecified"))
    )
    (net (code "70") (name "unconnected-(R16-Pad2)") (class "Default")
      (node (ref "R16") (pin "2") (pinfunction "2_2") (pintype "unspecified"))
    )
    (net (code "71") (name "unconnected-(R21-Pad1)") (class "Default")
      (node (ref "R21") (pin "1") (pinfunction "1_1") (pintype "unspecified"))
    )
    (net (code "72") (name "unconnected-(R22-Pad1)") (class "Default")
      (node (ref "R22") (pin "1") (pinfunction "1_1") (pintype "unspecified"))
    )
    (net (code "73") (name "unconnected-(SW1-Pad1)") (class "Default")
      (node (ref "SW1") (pin "1") (pinfunction "1_1") (pintype "unspecified"))
    )
    (net (code "74") (name "unconnected-(SW1-Pad4)") (class "Default")
      (node (ref "SW1") (pin "4") (pinfunction "4_4") (pintype "unspecified"))
    )
    (net (code "75") (name "unconnected-(SW1-Pad5)") (class "Default")
      (node (ref "SW1") (pin "5") (pinfunction "5_5") (pintype "unspecified"))
    )
    (net (code "76") (name "unconnected-(U1-PIN1-Pad1)") (class "Default")
      (node (ref "U1") (pin "1") (pinfunction "PIN1_1") (pintype "unspecified"))
    )
    (net (code "77") (name "unconnected-(U1-PIN7-Pad7)") (class "Default")
      (node (ref "U1") (pin "7") (pinfunction "PIN7_7") (pintype "unspecified"))
    )
    (net (code "78") (name "unconnected-(U1-PIN8-Pad8)") (class "Default")
      (node (ref "U1") (pin "8") (pinfunction "PIN8_8") (pintype "unspecified"))
    )
    (net (code "79") (name "unconnected-(U1-PIN12-Pad12)") (class "Default")
      (node (ref "U1") (pin "12") (pinfunction "PIN12_12") (pintype "unspecified"))
    )
    (net (code "80") (name "unconnected-(U1-PIN13-Pad13)") (class "Default")
      (node (ref "U1") (pin "13") (pinfunction "PIN13_13") (pintype "unspecified"))
    )
    (net (code "81") (name "unconnected-(U1-PIN21-Pad21)") (class "Default")
      (node (ref "U1") (pin "21") (pinfunction "PIN21_21") (pintype "unspecified"))
    )
    (net (code "82") (name "unconnected-(U1-PIN22-Pad22)") (class "Default")
      (node (ref "U1") (pin "22") (pinfunction "PIN22_22") (pintype "unspecified"))
    )
    (net (code "83") (name "unconnected-(U1-PIN23-Pad23)") (class "Default")
      (node (ref "U1") (pin "23") (pinfunction "PIN23_23") (pintype "unspecified"))
    )
    (net (code "84") (name "unconnected-(U1-PIN24-Pad24)") (class "Default")
      (node (ref "U1") (pin "24") (pinfunction "PIN24_24") (pintype "unspecified"))
    )
    (net (code "85") (name "unconnected-(U5-NC-Pad4)") (class "Default")
      (node (ref "U5") (pin "4") (pinfunction "NC_4") (pintype "unspecified"))
    )
    (net (code "86") (name "unconnected-(U10-NC-Pad4)") (class "Default")
      (node (ref "U10") (pin "4") (pinfunction "NC_4") (pintype "unspecified"))
    )
    (net (code "87") (name "unconnected-(U11-VSS-Pad8)") (class "Default")
      (node (ref "U11") (pin "8") (pinfunction "VSS_8") (pintype "unspecified"))
    )
    (net (code "88") (name "unconnected-(U11-VSS-Pad9)") (class "Default")
      (node (ref "U11") (pin "9") (pinfunction "VSS_9") (pintype "unspecified"))
    )
    (net (code "89") (name "unconnected-(U18-Pad1)") (class "Default")
      (node (ref "U18") (pin "1") (pinfunction "1_1") (pintype "unspecified"))
    )
    (net (code "90") (name "unconnected-(U18-Pad3)") (class "Default")
      (node (ref "U18") (pin "3") (pinfunction "3_3") (pintype "unspecified"))
    )
    (net (code "91") (name "unconnected-(U18-Pad4)") (class "Default")
      (node (ref "U18") (pin "4") (pinfunction "4_4") (pintype "unspecified"))
    )
    (net (code "92") (name "unconnected-(U21-EN-Pad3)") (class "Default")
      (node (ref "U21") (pin "3") (pinfunction "EN_3") (pintype "unspecified"))
    )
    (net (code "93") (name "unconnected-(U21-NC-Pad4)") (class "Default")
      (node (ref "U21") (pin "4") (pinfunction "NC_4") (pintype "unspecified"))
    )
    (net (code "94") (name "unconnected-(U22-AVCC-PadA2)") (class "Default")
      (node (ref "U22") (pin "A2") (pinfunction "AVCC_A2") (pintype "unspecified"))
    )
    (net (code "95") (name "unconnected-(U22-GND-PadA3)") (class "Default")
      (node (ref "U22") (pin "A3") (pinfunction "GND_A3") (pintype "unspecified"))
    )
    (net (code "96") (name "unconnected-(U22-GND-PadB4)") (class "Default")
      (node (ref "U22") (pin "B4") (pinfunction "GND_B4") (pintype "unspecified"))
    )
    (net (code "97") (name "unconnected-(U22-GND-PadC5)") (class "Default")
      (node (ref "U22") (pin "C5") (pinfunction "GND_C5") (pintype "unspecified"))
    )
    (net (code "98") (name "unconnected-(U22-GND-PadC7)") (class "Default")
      (node (ref "U22") (pin "C7") (pinfunction "GND_C7") (pintype "unspecified"))
    )
    (net (code "99") (name "unconnected-(U22-GND-PadD5)") (class "Default")
      (node (ref "U22") (pin "D5") (pinfunction "GND_D5") (pintype "unspecified"))
    )
    (net (code "100") (name "unconnected-(U22-GND-PadE1)") (class "Default")
      (node (ref "U22") (pin "E1") (pinfunction "GND_E1") (pintype "unspecified"))
    )
    (net (code "101") (name "unconnected-(U22-GND-PadE2)") (class "Default")
      (node (ref "U22") (pin "E2") (pinfunction "GND_E2") (pintype "unspecified"))
    )
    (net (code "102") (name "unconnected-(U22-GND-PadE4)") (class "Default")
      (node (ref "U22") (pin "E4") (pinfunction "GND_E4") (pintype "unspecified"))
    )
    (net (code "103") (name "unconnected-(U22-GND-PadG5)") (class "Default")
      (node (ref "U22") (pin "G5") (pinfunction "GND_G5") (pintype "unspecified"))
    )
    (net (code "104") (name "unconnected-(U22-PA0-PadB3)") (class "Default")
      (node (ref "U22") (pin "B3") (pinfunction "PA0_B3") (pintype "unspecified"))
    )
    (net (code "105") (name "unconnected-(U22-PA1-PadB2)") (class "Default")
      (node (ref "U22") (pin "B2") (pinfunction "PA1_B2") (pintype "unspecified"))
    )
    (net (code "106") (name "unconnected-(U22-PA2-PadC2)") (class "Default")
      (node (ref "U22") (pin "C2") (pinfunction "PA2_C2") (pintype "unspecified"))
    )
    (net (code "107") (name "unconnected-(U22-PA3-PadA1)") (class "Default")
      (node (ref "U22") (pin "A1") (pinfunction "PA3_A1") (pintype "unspecified"))
    )
    (net (code "108") (name "unconnected-(U22-PA4-PadB1)") (class "Default")
      (node (ref "U22") (pin "B1") (pinfunction "PA4_B1") (pintype "unspecified"))
    )
    (net (code "109") (name "unconnected-(U22-PA5-PadC1)") (class "Default")
      (node (ref "U22") (pin "C1") (pinfunction "PA5_C1") (pintype "unspecified"))
    )
    (net (code "110") (name "unconnected-(U22-PA6-PadC3)") (class "Default")
      (node (ref "U22") (pin "C3") (pinfunction "PA6_C3") (pintype "unspecified"))
    )
    (net (code "111") (name "unconnected-(U22-PA7-PadC4)") (class "Default")
      (node (ref "U22") (pin "C4") (pinfunction "PA7_C4") (pintype "unspecified"))
    )
    (net (code "112") (name "unconnected-(U22-PB0-PadD4)") (class "Default")
      (node (ref "U22") (pin "D4") (pinfunction "PB0_D4") (pintype "unspecified"))
    )
    (net (code "113") (name "unconnected-(U22-PB1-PadD1)") (class "Default")
      (node (ref "U22") (pin "D1") (pinfunction "PB1_D1") (pintype "unspecified"))
    )
    (net (code "114") (name "unconnected-(U22-PB2-PadD2)") (class "Default")
      (node (ref "U22") (pin "D2") (pinfunction "PB2_D2") (pintype "unspecified"))
    )
    (net (code "115") (name "unconnected-(U22-PB3-PadD3)") (class "Default")
      (node (ref "U22") (pin "D3") (pinfunction "PB3_D3") (pintype "unspecified"))
    )
    (net (code "116") (name "unconnected-(U22-PC0-PadF2)") (class "Default")
      (node (ref "U22") (pin "F2") (pinfunction "PC0_F2") (pintype "unspecified"))
    )
    (net (code "117") (name "unconnected-(U22-PC1-PadG1)") (class "Default")
      (node (ref "U22") (pin "G1") (pinfunction "PC1_G1") (pintype "unspecified"))
    )
    (net (code "118") (name "unconnected-(U22-PC2-PadG2)") (class "Default")
      (node (ref "U22") (pin "G2") (pinfunction "PC2_G2") (pintype "unspecified"))
    )
    (net (code "119") (name "unconnected-(U22-PC3-PadE3)") (class "Default")
      (node (ref "U22") (pin "E3") (pinfunction "PC3_E3") (pintype "unspecified"))
    )
    (net (code "120") (name "unconnected-(U22-PC4-PadF3)") (class "Default")
      (node (ref "U22") (pin "F3") (pinfunction "PC4_F3") (pintype "unspecified"))
    )
    (net (code "121") (name "unconnected-(U22-PC5-PadG3)") (class "Default")
      (node (ref "U22") (pin "G3") (pinfunction "PC5_G3") (pintype "unspecified"))
    )
    (net (code "122") (name "unconnected-(U22-PC6-PadF4)") (class "Default")
      (node (ref "U22") (pin "F4") (pinfunction "PC6_F4") (pintype "unspecified"))
    )
    (net (code "123") (name "unconnected-(U22-PC7-PadG4)") (class "Default")
      (node (ref "U22") (pin "G4") (pinfunction "PC7_G4") (pintype "unspecified"))
    )
    (net (code "124") (name "unconnected-(U22-PD0-PadF5)") (class "Default")
      (node (ref "U22") (pin "F5") (pinfunction "PD0_F5") (pintype "unspecified"))
    )
    (net (code "125") (name "unconnected-(U22-PD1-PadF6)") (class "Default")
      (node (ref "U22") (pin "F6") (pinfunction "PD1_F6") (pintype "unspecified"))
    )
    (net (code "126") (name "unconnected-(U22-PD2-PadG7)") (class "Default")
      (node (ref "U22") (pin "G7") (pinfunction "PD2_G7") (pintype "unspecified"))
    )
    (net (code "127") (name "unconnected-(U22-PD3-PadF7)") (class "Default")
      (node (ref "U22") (pin "F7") (pinfunction "PD3_F7") (pintype "unspecified"))
    )
    (net (code "128") (name "unconnected-(U22-PD4-PadE5)") (class "Default")
      (node (ref "U22") (pin "E5") (pinfunction "PD4_E5") (pintype "unspecified"))
    )
    (net (code "129") (name "unconnected-(U22-PD5-PadE6)") (class "Default")
      (node (ref "U22") (pin "E6") (pinfunction "PD5_E6") (pintype "unspecified"))
    )
    (net (code "130") (name "unconnected-(U22-PD6-PadE7)") (class "Default")
      (node (ref "U22") (pin "E7") (pinfunction "PD6_E7") (pintype "unspecified"))
    )
    (net (code "131") (name "unconnected-(U22-PD7-PadD6)") (class "Default")
      (node (ref "U22") (pin "D6") (pinfunction "PD7_D6") (pintype "unspecified"))
    )
    (net (code "132") (name "unconnected-(U22-PDI-PadA6)") (class "Default")
      (node (ref "U22") (pin "A6") (pinfunction "PDI_A6") (pintype "unspecified"))
    )
    (net (code "133") (name "unconnected-(U22-PE0-PadD7)") (class "Default")
      (node (ref "U22") (pin "D7") (pinfunction "PE0_D7") (pintype "unspecified"))
    )
    (net (code "134") (name "unconnected-(U22-PE1-PadC6)") (class "Default")
      (node (ref "U22") (pin "C6") (pinfunction "PE1_C6") (pintype "unspecified"))
    )
    (net (code "135") (name "unconnected-(U22-PE2-PadB6)") (class "Default")
      (node (ref "U22") (pin "B6") (pinfunction "PE2_B6") (pintype "unspecified"))
    )
    (net (code "136") (name "unconnected-(U22-PE3-PadA7)") (class "Default")
      (node (ref "U22") (pin "A7") (pinfunction "PE3_A7") (pintype "unspecified"))
    )
    (net (code "137") (name "unconnected-(U22-PR0-PadA5)") (class "Default")
      (node (ref "U22") (pin "A5") (pinfunction "PR0_A5") (pintype "unspecified"))
    )
    (net (code "138") (name "unconnected-(U22-PR1-PadA4)") (class "Default")
      (node (ref "U22") (pin "A4") (pinfunction "PR1_A4") (pintype "unspecified"))
    )
    (net (code "139") (name "unconnected-(U22-RESET#{slash}PDI_CLK-PadB5)") (class "Default")
      (node (ref "U22") (pin "B5") (pinfunction "RESET#/PDI_CLK_B5") (pintype "unspecified"))
    )
    (net (code "140") (name "unconnected-(U22-VCC-PadB7)") (class "Default")
      (node (ref "U22") (pin "B7") (pinfunction "VCC_B7") (pintype "unspecified"))
    )
    (net (code "141") (name "unconnected-(U22-VCC-PadF1)") (class "Default")
      (node (ref "U22") (pin "F1") (pinfunction "VCC_F1") (pintype "unspecified"))
    )
    (net (code "142") (name "unconnected-(U22-VCC-PadG6)") (class "Default")
      (node (ref "U22") (pin "G6") (pinfunction "VCC_G6") (pintype "unspecified"))
    )
    (net (code "143") (name "unconnected-(U23-+-Pad1)") (class "Default")
      (node (ref "U23") (pin "1") (pinfunction "+_1") (pintype "unspecified"))
    )
    (net (code "144") (name "unconnected-(U24-ANT-Pad21)") (class "Default")
      (node (ref "U24") (pin "21") (pinfunction "ANT_21") (pintype "unspecified"))
    )
    (net (code "145") (name "unconnected-(U24-BUSY-Pad10)") (class "Default")
      (node (ref "U24") (pin "10") (pinfunction "BUSY_10") (pintype "unspecified"))
    )
    (net (code "146") (name "unconnected-(U24-DIO1-Pad5)") (class "Default")
      (node (ref "U24") (pin "5") (pinfunction "DIO1_5") (pintype "unspecified"))
    )
    (net (code "147") (name "unconnected-(U24-DIO3-Pad8)") (class "Default")
      (node (ref "U24") (pin "8") (pinfunction "DIO3_8") (pintype "unspecified"))
    )
    (net (code "148") (name "unconnected-(U24-MISO-Pad15)") (class "Default")
      (node (ref "U24") (pin "15") (pinfunction "MISO_15") (pintype "unspecified"))
    )
    (net (code "149") (name "unconnected-(U24-MOSI-Pad16)") (class "Default")
      (node (ref "U24") (pin "16") (pinfunction "MOSI_16") (pintype "unspecified"))
    )
    (net (code "150") (name "unconnected-(U24-NC-Pad6)") (class "Default")
      (node (ref "U24") (pin "6") (pinfunction "NC_6") (pintype "unspecified"))
    )
    (net (code "151") (name "unconnected-(U24-NC-Pad7)") (class "Default")
      (node (ref "U24") (pin "7") (pinfunction "NC_7") (pintype "unspecified"))
    )
    (net (code "152") (name "unconnected-(U24-NC-Pad9)") (class "Default")
      (node (ref "U24") (pin "9") (pinfunction "NC_9") (pintype "unspecified"))
    )
    (net (code "153") (name "unconnected-(U24-RST-Pad18)") (class "Default")
      (node (ref "U24") (pin "18") (pinfunction "RST_18") (pintype "unspecified"))
    )
    (net (code "154") (name "unconnected-(U24-SCK-Pad14)") (class "Default")
      (node (ref "U24") (pin "14") (pinfunction "SCK_14") (pintype "unspecified"))
    )
    (net (code "155") (name "unconnected-(U24-SEL-Pad17)") (class "Default")
      (node (ref "U24") (pin "17") (pinfunction "SEL_17") (pintype "unspecified"))
    )
  )
)
